# ClassDesign.net
KiCad netlist of a schematic drawn in Altium Designer
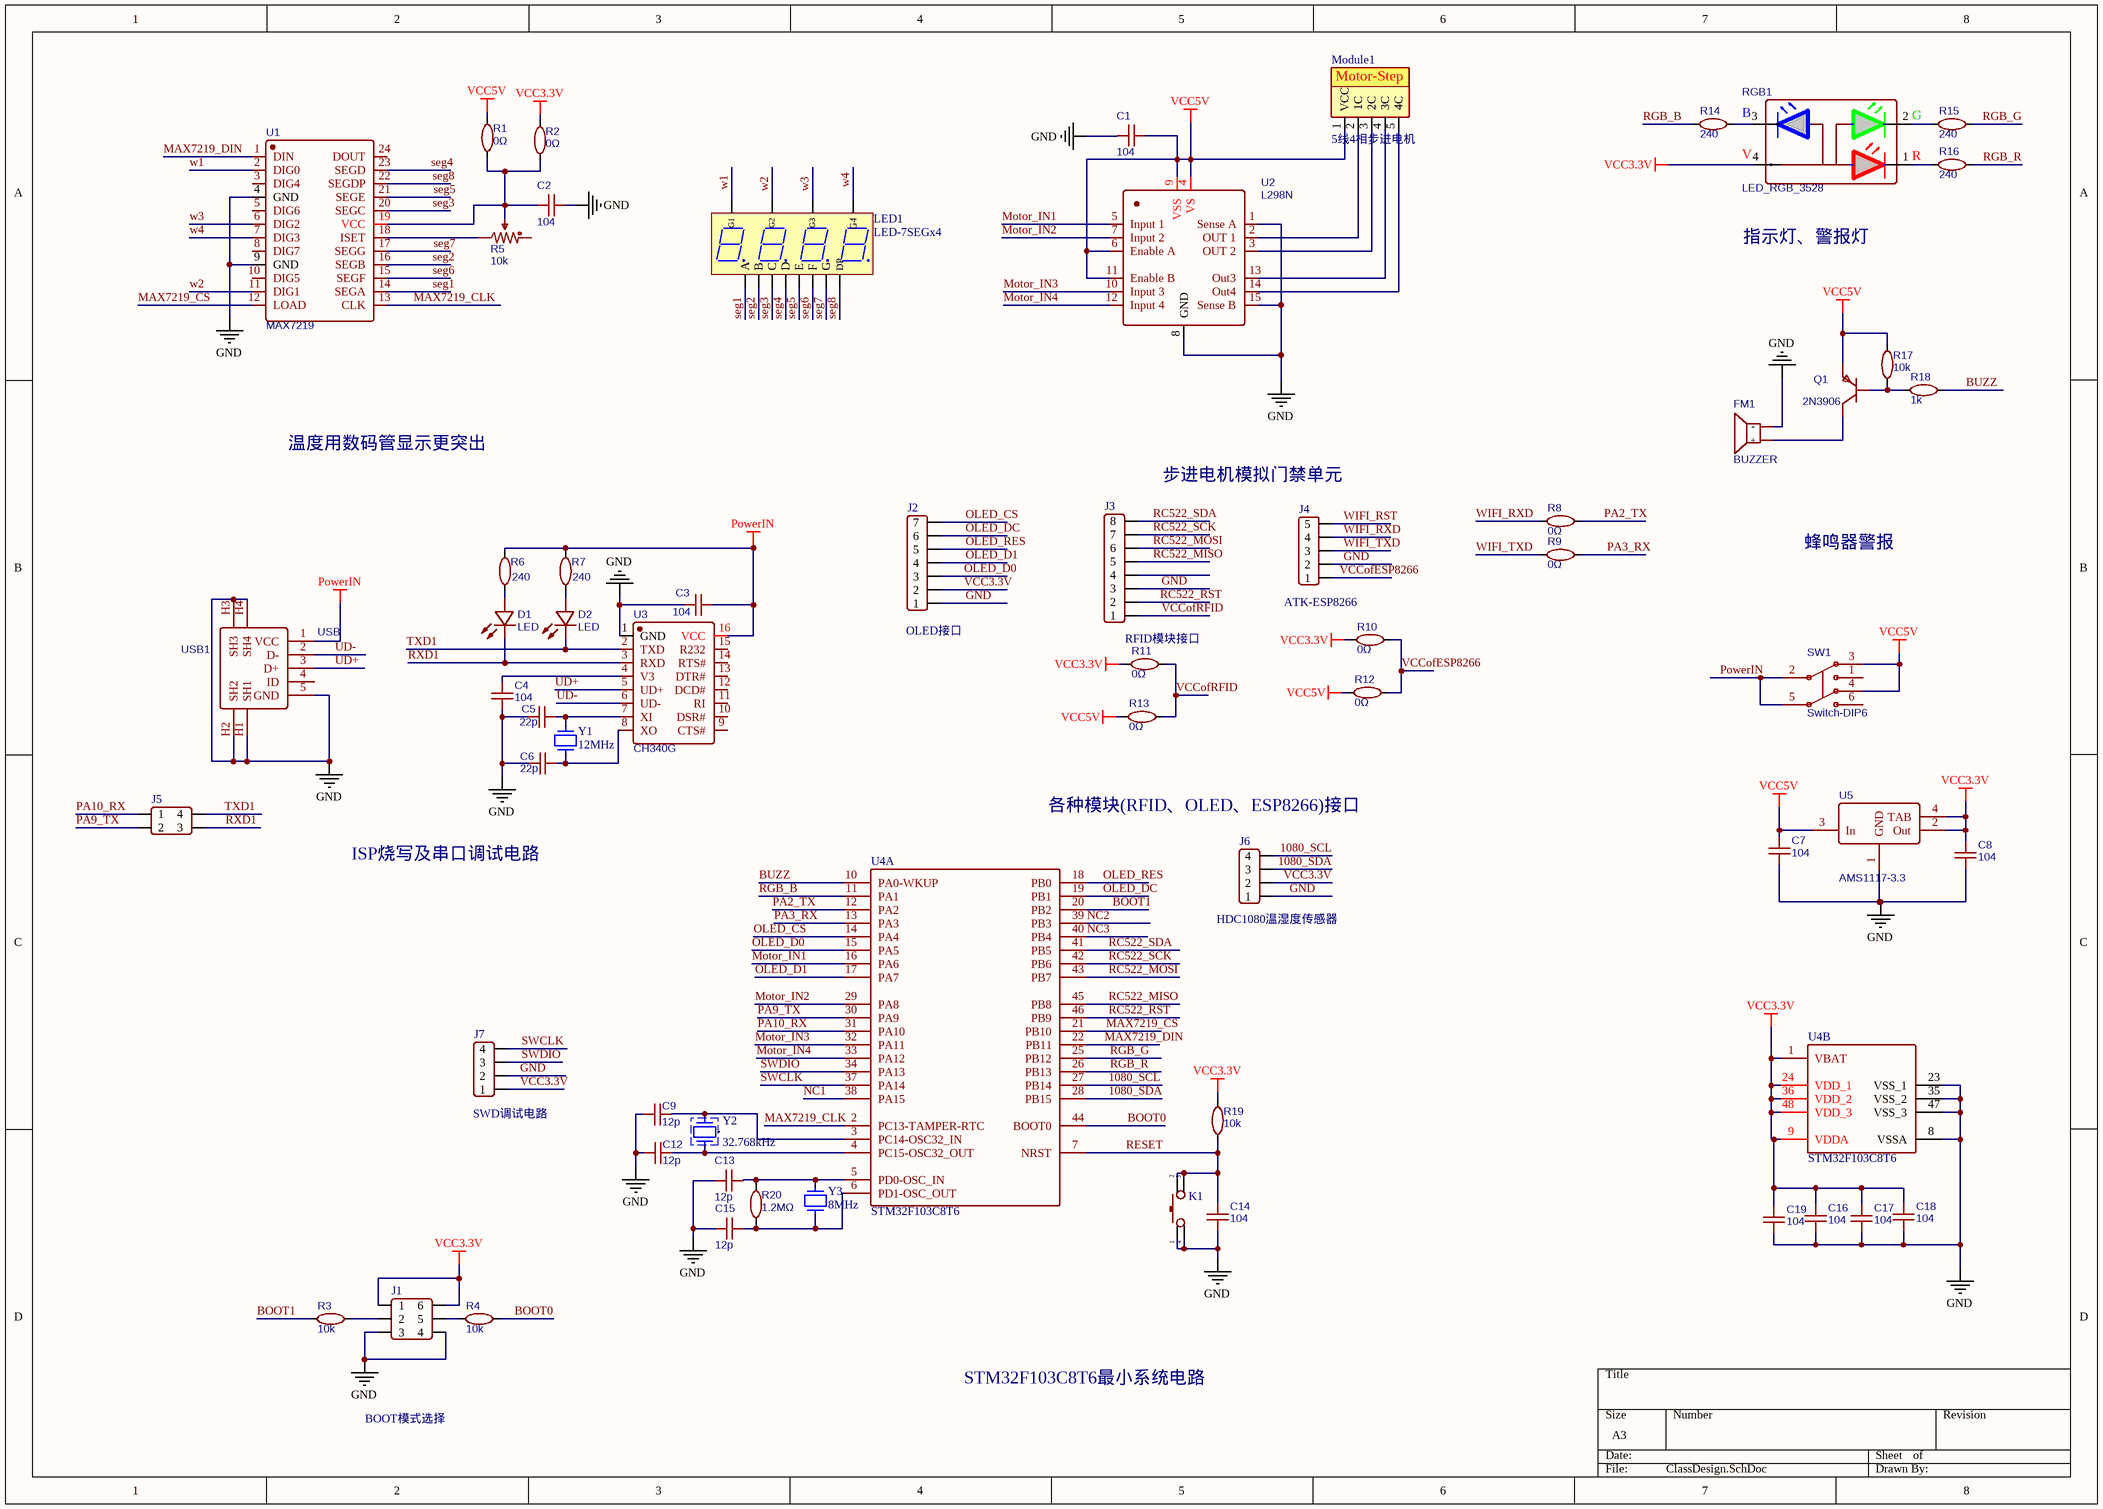
[diagram p0: ClassDesign.SchDoc]

(export (version "E")
  (design (tool "Eeschema 10.0.6"))
  (components
    (comp (ref "C1")
      (value "104")
      (footprint "CAP_0805")
      (fields
        (field (name "BOM_SUPPLIER PART") "C307348")
        (field (name "BOM_MANUFACTURER PART") "CL10B104KB8WPNC")
        (field (name "CONTRIBUTOR") "LCSC")
      )
      (libsource (lib "LTC_Library1") (part "CAP_0805"))
    )
    (comp (ref "C2")
      (value "104")
      (footprint "CAP_0805")
      (fields
        (field (name "BOM_SUPPLIER PART") "C307348")
        (field (name "BOM_MANUFACTURER PART") "CL10B104KB8WPNC")
        (field (name "CONTRIBUTOR") "LCSC")
      )
      (libsource (lib "LTC_Library1") (part "CAP_0805"))
    )
    (comp (ref "C3")
      (value "104")
      (footprint "CAP_0805")
      (fields
        (field (name "BOM_SUPPLIER PART") "C307348")
        (field (name "BOM_MANUFACTURER PART") "CL10B104KB8WPNC")
        (field (name "CONTRIBUTOR") "LCSC")
      )
      (libsource (lib "LTC_Library1") (part "CAP_0805"))
    )
    (comp (ref "C4")
      (value "104")
      (footprint "CAP_0805")
      (fields
        (field (name "BOM_SUPPLIER PART") "C307348")
        (field (name "BOM_MANUFACTURER PART") "CL10B104KB8WPNC")
        (field (name "CONTRIBUTOR") "LCSC")
      )
      (libsource (lib "LTC_Library1") (part "CAP_0805"))
    )
    (comp (ref "C5")
      (value "22p")
      (footprint "CAP_0805")
      (fields
        (field (name "BOM_SUPPLIER PART") "C307348")
        (field (name "BOM_MANUFACTURER PART") "CL10B104KB8WPNC")
        (field (name "CONTRIBUTOR") "LCSC")
      )
      (libsource (lib "LTC_Library1") (part "CAP_0805"))
    )
    (comp (ref "C6")
      (value "22p")
      (footprint "CAP_0805")
      (fields
        (field (name "BOM_SUPPLIER PART") "C307348")
        (field (name "BOM_MANUFACTURER PART") "CL10B104KB8WPNC")
        (field (name "CONTRIBUTOR") "LCSC")
      )
      (libsource (lib "LTC_Library1") (part "CAP_0805"))
    )
    (comp (ref "C7")
      (value "104")
      (footprint "CAP_0805")
      (fields
        (field (name "BOM_SUPPLIER PART") "C307348")
        (field (name "BOM_MANUFACTURER PART") "CL10B104KB8WPNC")
        (field (name "CONTRIBUTOR") "LCSC")
      )
      (libsource (lib "LTC_Library1") (part "CAP_0805"))
    )
    (comp (ref "C8")
      (value "104")
      (footprint "CAP_0805")
      (fields
        (field (name "BOM_SUPPLIER PART") "C307348")
        (field (name "BOM_MANUFACTURER PART") "CL10B104KB8WPNC")
        (field (name "CONTRIBUTOR") "LCSC")
      )
      (libsource (lib "LTC_Library1") (part "CAP_0805"))
    )
    (comp (ref "C9")
      (value "12p")
      (footprint "CAP_0805")
      (fields
        (field (name "BOM_SUPPLIER PART") "C307348")
        (field (name "BOM_MANUFACTURER PART") "CL10B104KB8WPNC")
        (field (name "CONTRIBUTOR") "LCSC")
      )
      (libsource (lib "LTC_Library1") (part "CAP_0805"))
    )
    (comp (ref "C12")
      (value "12p")
      (footprint "CAP_0805")
      (fields
        (field (name "BOM_SUPPLIER PART") "C307348")
        (field (name "BOM_MANUFACTURER PART") "CL10B104KB8WPNC")
        (field (name "CONTRIBUTOR") "LCSC")
      )
      (libsource (lib "LTC_Library1") (part "CAP_0805"))
    )
    (comp (ref "C13")
      (value "12p")
      (footprint "CAP_0805")
      (fields
        (field (name "BOM_SUPPLIER PART") "C307348")
        (field (name "BOM_MANUFACTURER PART") "CL10B104KB8WPNC")
        (field (name "CONTRIBUTOR") "LCSC")
      )
      (libsource (lib "LTC_Library1") (part "CAP_0805"))
    )
    (comp (ref "C14")
      (value "104")
      (footprint "CAP_0805")
      (fields
        (field (name "BOM_SUPPLIER PART") "C307348")
        (field (name "BOM_MANUFACTURER PART") "CL10B104KB8WPNC")
        (field (name "CONTRIBUTOR") "LCSC")
      )
      (libsource (lib "LTC_Library1") (part "CAP_0805"))
    )
    (comp (ref "C15")
      (value "12p")
      (footprint "CAP_0805")
      (fields
        (field (name "BOM_SUPPLIER PART") "C307348")
        (field (name "BOM_MANUFACTURER PART") "CL10B104KB8WPNC")
        (field (name "CONTRIBUTOR") "LCSC")
      )
      (libsource (lib "LTC_Library1") (part "CAP_0805"))
    )
    (comp (ref "C16")
      (value "104")
      (footprint "CAP_0805")
      (fields
        (field (name "BOM_SUPPLIER PART") "C307348")
        (field (name "BOM_MANUFACTURER PART") "CL10B104KB8WPNC")
        (field (name "CONTRIBUTOR") "LCSC")
      )
      (libsource (lib "LTC_Library1") (part "CAP_0805"))
    )
    (comp (ref "C17")
      (value "104")
      (footprint "CAP_0805")
      (fields
        (field (name "BOM_SUPPLIER PART") "C307348")
        (field (name "BOM_MANUFACTURER PART") "CL10B104KB8WPNC")
        (field (name "CONTRIBUTOR") "LCSC")
      )
      (libsource (lib "LTC_Library1") (part "CAP_0805"))
    )
    (comp (ref "C18")
      (value "104")
      (footprint "CAP_0805")
      (fields
        (field (name "BOM_SUPPLIER PART") "C307348")
        (field (name "BOM_MANUFACTURER PART") "CL10B104KB8WPNC")
        (field (name "CONTRIBUTOR") "LCSC")
      )
      (libsource (lib "LTC_Library1") (part "CAP_0805"))
    )
    (comp (ref "C19")
      (value "104")
      (footprint "CAP_0805")
      (fields
        (field (name "BOM_SUPPLIER PART") "C307348")
        (field (name "BOM_MANUFACTURER PART") "CL10B104KB8WPNC")
        (field (name "CONTRIBUTOR") "LCSC")
      )
      (libsource (lib "LTC_Library1") (part "CAP_0805"))
    )
    (comp (ref "D1")
      (value "LED")
      (footprint "LED_0805_R")
      (description "发光LED")
      (fields
        (field (name "BOM_MANUFACTURER PART") "D-G080508G1")
        (field (name "BOM_SUPPLIER PART") "C107402")
        (field (name "CONTRIBUTOR") "LCSC")
      )
      (libsource (lib "LTC_Library1") (part "LED_0805"))
    )
    (comp (ref "D2")
      (value "LED")
      (footprint "LED_0805_R")
      (description "发光LED")
      (fields
        (field (name "BOM_MANUFACTURER PART") "D-G080508G1")
        (field (name "BOM_SUPPLIER PART") "C107402")
        (field (name "CONTRIBUTOR") "LCSC")
      )
      (libsource (lib "LTC_Library1") (part "LED_0805"))
    )
    (comp (ref "FM1")
      (value "BUZZER")
      (footprint "BUZZ-12*7.5")
      (description "蜂鸣器")
      (fields (field (name "BOM_MANUFACTURER PART") "TMB12A12") (field (name "BOM_SUPPLIER PART") "C96079"))
      (libsource (lib "LTC_Library1") (part "BUZZER"))
    )
    (comp (ref "J1")
      (value "BOOT模式选择")
      (footprint "Header 2.54_2X3")
      (libsource (lib "LTC_Library1") (part "Header 2.54_2X3"))
    )
    (comp (ref "J2")
      (value "OLED接口")
      (footprint "Header 2.54X7")
      (libsource (lib "LTC_Library1") (part "Header 2.54_7"))
    )
    (comp (ref "J3")
      (value "RFID模块接口")
      (footprint "Header 2.54X8")
      (libsource (lib "Headers") (part "Header 2.54_8"))
    )
    (comp (ref "J4")
      (value "ATK-ESP8266")
      (footprint "Header 2.54X5")
      (libsource (lib "Headers") (part "Header 2.54_5"))
    )
    (comp (ref "J5")
      (value "Header 2.54_2X2")
      (footprint "Header 2.54_2x2")
      (libsource (lib "LTC_Library1") (part "Header 2.54_2X2"))
    )
    (comp (ref "J6")
      (value "HDC1080温湿度传感器")
      (footprint "Header 2.54X4")
      (libsource (lib "LTC_Library1") (part "Header 2.54_4"))
    )
    (comp (ref "J7")
      (value "SWD调试电路")
      (footprint "Header 2.54X4")
      (libsource (lib "LTC_Library1") (part "Header 2.54_4"))
    )
    (comp (ref "K1")
      (value "DIP-Button_4P")
      (footprint "TSW DIP-6*6*6")
      (description "按键，直插，6*6*6")
      (libsource (lib "LTC_Library1") (part "DIP-Button_4P"))
    )
    (comp (ref "LED1")
      (value "LED-7SEGx4")
      (footprint "DISP_0.56_4")
      (libsource (lib "LTC_Library1") (part "LED-7SEGx4"))
    )
    (comp (ref "Module1")
      (value "5线4相步进电机")
      (footprint "XH_2.54_5P")
      (libsource (lib "Module") (part "5线4相步进电机"))
    )
    (comp (ref "Q1")
      (value "2N3906")
      (footprint "TO_92A")
      (description "三极管PNP")
      (fields (field (name "BOM_SUPPLIER PART") "C305396") (field (name "CONTRIBUTOR") "LCSC"))
      (libsource (lib "LTC_Library1") (part "2N3906"))
    )
    (comp (ref "R1")
      (value "0Ω")
      (footprint "RES_0805")
      (fields
        (field (name "BOM_MANUFACTURER PART") "RC0402JR-07100KL")
        (field (name "BOM_SUPPLIER PART") "C106234")
      )
      (libsource (lib "LTC_Library1") (part "RES_0805"))
    )
    (comp (ref "R2")
      (value "0Ω")
      (footprint "RES_0805")
      (fields
        (field (name "BOM_MANUFACTURER PART") "RC0402JR-07100KL")
        (field (name "BOM_SUPPLIER PART") "C106234")
      )
      (libsource (lib "LTC_Library1") (part "RES_0805"))
    )
    (comp (ref "R3")
      (value "10k")
      (footprint "RES_0805")
      (fields
        (field (name "BOM_MANUFACTURER PART") "RC0402JR-07100KL")
        (field (name "BOM_SUPPLIER PART") "C106234")
      )
      (libsource (lib "LTC_Library1") (part "RES_0805"))
    )
    (comp (ref "R4")
      (value "10k")
      (footprint "RES_0805")
      (fields
        (field (name "BOM_MANUFACTURER PART") "RC0402JR-07100KL")
        (field (name "BOM_SUPPLIER PART") "C106234")
      )
      (libsource (lib "LTC_Library1") (part "RES_0805"))
    )
    (comp (ref "R5")
      (value "10k")
      (footprint "RES_POT-3362P")
      (description "可调电阻3362P")
      (fields
        (field (name "BOM_SUPPLIER PART") "C118947")
        (field (name "BOM_MANUFACTURER PART") "3362P-1-102")
        (field (name "CONTRIBUTOR") "LCSC")
      )
      (libsource (lib "LTC_Library1") (part "RES_POT-3362P"))
    )
    (comp (ref "R6")
      (value "240")
      (footprint "RES_0805")
      (fields
        (field (name "BOM_MANUFACTURER PART") "RC0402JR-07100KL")
        (field (name "BOM_SUPPLIER PART") "C106234")
      )
      (libsource (lib "LTC_Library1") (part "RES_0805"))
    )
    (comp (ref "R7")
      (value "240")
      (footprint "RES_0805")
      (fields
        (field (name "BOM_MANUFACTURER PART") "RC0402JR-07100KL")
        (field (name "BOM_SUPPLIER PART") "C106234")
      )
      (libsource (lib "LTC_Library1") (part "RES_0805"))
    )
    (comp (ref "R8")
      (value "0Ω")
      (footprint "RES_0805")
      (fields
        (field (name "BOM_MANUFACTURER PART") "RC0402JR-07100KL")
        (field (name "BOM_SUPPLIER PART") "C106234")
      )
      (libsource (lib "LTC_Library1") (part "RES_0805"))
    )
    (comp (ref "R9")
      (value "0Ω")
      (footprint "RES_0805")
      (fields
        (field (name "BOM_MANUFACTURER PART") "RC0402JR-07100KL")
        (field (name "BOM_SUPPLIER PART") "C106234")
      )
      (libsource (lib "LTC_Library1") (part "RES_0805"))
    )
    (comp (ref "R10")
      (value "0Ω")
      (footprint "RES_0805")
      (fields
        (field (name "BOM_MANUFACTURER PART") "RC0402JR-07100KL")
        (field (name "BOM_SUPPLIER PART") "C106234")
      )
      (libsource (lib "LTC_Library1") (part "RES_0805"))
    )
    (comp (ref "R11")
      (value "0Ω")
      (footprint "RES_0805")
      (fields
        (field (name "BOM_MANUFACTURER PART") "RC0402JR-07100KL")
        (field (name "BOM_SUPPLIER PART") "C106234")
      )
      (libsource (lib "LTC_Library1") (part "RES_0805"))
    )
    (comp (ref "R12")
      (value "0Ω")
      (footprint "RES_0805")
      (fields
        (field (name "BOM_MANUFACTURER PART") "RC0402JR-07100KL")
        (field (name "BOM_SUPPLIER PART") "C106234")
      )
      (libsource (lib "LTC_Library1") (part "RES_0805"))
    )
    (comp (ref "R13")
      (value "0Ω")
      (footprint "RES_0805")
      (fields
        (field (name "BOM_MANUFACTURER PART") "RC0402JR-07100KL")
        (field (name "BOM_SUPPLIER PART") "C106234")
      )
      (libsource (lib "LTC_Library1") (part "RES_0805"))
    )
    (comp (ref "R14")
      (value "240")
      (footprint "RES_0805")
      (fields
        (field (name "BOM_MANUFACTURER PART") "RC0402JR-07100KL")
        (field (name "BOM_SUPPLIER PART") "C106234")
      )
      (libsource (lib "LTC_Library1") (part "RES_0805"))
    )
    (comp (ref "R15")
      (value "240")
      (footprint "RES_0805")
      (fields
        (field (name "BOM_MANUFACTURER PART") "RC0402JR-07100KL")
        (field (name "BOM_SUPPLIER PART") "C106234")
      )
      (libsource (lib "LTC_Library1") (part "RES_0805"))
    )
    (comp (ref "R16")
      (value "240")
      (footprint "RES_0805")
      (fields
        (field (name "BOM_MANUFACTURER PART") "RC0402JR-07100KL")
        (field (name "BOM_SUPPLIER PART") "C106234")
      )
      (libsource (lib "LTC_Library1") (part "RES_0805"))
    )
    (comp (ref "R17")
      (value "10k")
      (footprint "RES_0805")
      (fields
        (field (name "BOM_MANUFACTURER PART") "RC0402JR-07100KL")
        (field (name "BOM_SUPPLIER PART") "C106234")
      )
      (libsource (lib "LTC_Library1") (part "RES_0805"))
    )
    (comp (ref "R18")
      (value "1k")
      (footprint "RES_0805")
      (fields
        (field (name "BOM_MANUFACTURER PART") "RC0402JR-07100KL")
        (field (name "BOM_SUPPLIER PART") "C106234")
      )
      (libsource (lib "LTC_Library1") (part "RES_0805"))
    )
    (comp (ref "R19")
      (value "10k")
      (footprint "RES_0805")
      (fields
        (field (name "BOM_MANUFACTURER PART") "RC0402JR-07100KL")
        (field (name "BOM_SUPPLIER PART") "C106234")
      )
      (libsource (lib "LTC_Library1") (part "RES_0805"))
    )
    (comp (ref "R20")
      (value "1.2MΩ")
      (footprint "RES_0805")
      (fields
        (field (name "BOM_MANUFACTURER PART") "RC0402JR-07100KL")
        (field (name "BOM_SUPPLIER PART") "C106234")
      )
      (libsource (lib "LTC_Library1") (part "RES_0805"))
    )
    (comp (ref "RGB1")
      (value "LED_RGB_3528")
      (footprint "LED_3528_RGB")
      (fields
        (field (name "BOM_MANUFACTURER PART") "FM-3528RGBA-HF")
        (field (name "BOM_SUPPLIER PART") "C108539")
        (field (name "CONTRIBUTOR") "LCSC")
      )
      (libsource (lib "LTC_Library1") (part "LED_RGB_3528"))
    )
    (comp (ref "SW1")
      (value "Switch-DIP6")
      (footprint "Switch_6")
      (description "6脚自锁开关")
      (fields (field (name "BOM_MANUFACTURER PART") "ESB33535") (field (name "BOM_SUPPLIER PART") "C79134"))
      (libsource (lib "LTC_Library1") (part "Switch-DIP6"))
    )
    (comp (ref "U1")
      (value "MAX7219")
      (footprint "SOIC_24W")
      (fields (field (name "BOM_MANUFACTURER PART") "max7219cng") (field (name "BOM_SUPPLIER PART") "C29160"))
      (libsource (lib "LTC_Library1") (part "MAX7219"))
    )
    (comp (ref "U2")
      (value "L298N")
      (footprint "Multiwatt_15")
      (fields (field (name "BOM_SUPPLIER PART") "C434589") (field (name "CONTRIBUTOR") "LCSC"))
      (libsource (lib "Driver IC") (part "L298N"))
    )
    (comp (ref "U3")
      (value "CH340G")
      (footprint "SOP-16")
      (fields (field (name "BOM_SUPPLIER PART") "C14267"))
      (libsource (lib "LTC_Library1") (part "CH340G"))
    )
    (comp (ref "U4")
      (value "STM32F103C8T6")
      (footprint "LQFP_48_7X7")
      (libsource (lib "MCU") (part "STM32F103C8T6"))
    )
    (comp (ref "U5")
      (value "AMS1117-3.3")
      (footprint "SOT-223_3")
      (fields (field (name "BOM_SUPPLIER PART") "C165482") (field (name "CONTRIBUTOR") "LCSC"))
      (libsource (lib "LTC_Library1") (part "AMS1117-3.3"))
    )
    (comp (ref "USB1")
      (value "USB")
      (footprint "USB_Micro_DIP41")
      (fields
        (field (name "BOM_SUPPLIER PART") "C404969")
        (field (name "BOM_MANUFACTURER PART") "MicroXNJ")
        (field (name "CONTRIBUTOR") "LCSC")
      )
      (libsource (lib "LTC_Library1") (part "MicroUSB"))
    )
    (comp (ref "Y1")
      (value "12MHz")
      (footprint "XTAL1")
      (description "晶振")
      (libsource (lib "LTC_Library1") (part "XTAL-2"))
    )
    (comp (ref "Y2")
      (value "32.768kHz")
      (footprint "XTAL-D2X6")
      (description "晶振3脚")
      (libsource (lib "LTC_Library1") (part "XTAL-3"))
    )
    (comp (ref "Y3")
      (value "8MHz")
      (footprint "XTAL1")
      (description "晶振")
      (libsource (lib "LTC_Library1") (part "XTAL-2"))
    )
  )
  (nets
    (net (code "1") (name "/1080_SCL") (class "Default")
      (node (ref "J6") (pin "4") (pinfunction "4_4") (pintype "passive"))
      (node (ref "U4") (pin "27") (pinfunction "PB14_27") (pintype "passive"))
    )
    (net (code "2") (name "/1080_SDA") (class "Default")
      (node (ref "J6") (pin "3") (pinfunction "3_3") (pintype "passive"))
      (node (ref "U4") (pin "28") (pinfunction "PB15_28") (pintype "passive"))
    )
    (net (code "3") (name "/BOOT0") (class "Default")
      (node (ref "R4") (pin "2") (pinfunction "2_2") (pintype "passive"))
      (node (ref "U4") (pin "44") (pinfunction "BOOT0_44") (pintype "passive"))
    )
    (net (code "4") (name "/BOOT1") (class "Default")
      (node (ref "R3") (pin "1") (pinfunction "1_1") (pintype "passive"))
      (node (ref "U4") (pin "20") (pinfunction "PB2_20") (pintype "passive"))
    )
    (net (code "5") (name "/BUZZ") (class "Default")
      (node (ref "R18") (pin "2") (pinfunction "2_2") (pintype "passive"))
      (node (ref "U4") (pin "10") (pinfunction "PA0-WKUP_10") (pintype "passive"))
    )
    (net (code "6") (name "/MAX7219_CLK") (class "Default")
      (node (ref "U1") (pin "13") (pinfunction "CLK_13") (pintype "passive"))
      (node (ref "U4") (pin "2") (pinfunction "PC13-TAMPER-RTC_2") (pintype "passive"))
    )
    (net (code "7") (name "/MAX7219_CS") (class "Default")
      (node (ref "U1") (pin "12") (pinfunction "LOAD_12") (pintype "passive"))
      (node (ref "U4") (pin "21") (pinfunction "PB10_21") (pintype "passive"))
    )
    (net (code "8") (name "/MAX7219_DIN") (class "Default")
      (node (ref "U1") (pin "1") (pinfunction "DIN_1") (pintype "passive"))
      (node (ref "U4") (pin "22") (pinfunction "PB11_22") (pintype "passive"))
    )
    (net (code "9") (name "/Motor_IN1") (class "Default")
      (node (ref "U2") (pin "5") (pinfunction "Input_1_5") (pintype "passive"))
      (node (ref "U4") (pin "16") (pinfunction "PA6_16") (pintype "passive"))
    )
    (net (code "10") (name "/Motor_IN2") (class "Default")
      (node (ref "U2") (pin "7") (pinfunction "Input_2_7") (pintype "passive"))
      (node (ref "U4") (pin "29") (pinfunction "PA8_29") (pintype "passive"))
    )
    (net (code "11") (name "/Motor_IN3") (class "Default")
      (node (ref "U2") (pin "10") (pinfunction "Input_3_10") (pintype "passive"))
      (node (ref "U4") (pin "32") (pinfunction "PA11_32") (pintype "passive"))
    )
    (net (code "12") (name "/Motor_IN4") (class "Default")
      (node (ref "U2") (pin "12") (pinfunction "Input_4_12") (pintype "passive"))
      (node (ref "U4") (pin "33") (pinfunction "PA12_33") (pintype "passive"))
    )
    (net (code "13") (name "/NC1") (class "Default")
      (node (ref "U4") (pin "38") (pinfunction "PA15_38") (pintype "passive"))
    )
    (net (code "14") (name "/NC2") (class "Default")
      (node (ref "U4") (pin "39") (pinfunction "PB3_39") (pintype "passive"))
    )
    (net (code "15") (name "/NC3") (class "Default")
      (node (ref "U4") (pin "40") (pinfunction "PB4_40") (pintype "passive"))
    )
    (net (code "16") (name "/OLED_CS") (class "Default")
      (node (ref "J2") (pin "7") (pinfunction "7_7") (pintype "passive"))
      (node (ref "U4") (pin "14") (pinfunction "PA4_14") (pintype "passive"))
    )
    (net (code "17") (name "/OLED_D0") (class "Default")
      (node (ref "J2") (pin "3") (pinfunction "3_3") (pintype "passive"))
      (node (ref "U4") (pin "15") (pinfunction "PA5_15") (pintype "passive"))
    )
    (net (code "18") (name "/OLED_D1") (class "Default")
      (node (ref "J2") (pin "4") (pinfunction "4_4") (pintype "passive"))
      (node (ref "U4") (pin "17") (pinfunction "PA7_17") (pintype "passive"))
    )
    (net (code "19") (name "/OLED_DC") (class "Default")
      (node (ref "J2") (pin "6") (pinfunction "6_6") (pintype "passive"))
      (node (ref "U4") (pin "19") (pinfunction "PB1_19") (pintype "passive"))
    )
    (net (code "20") (name "/OLED_RES") (class "Default")
      (node (ref "J2") (pin "5") (pinfunction "5_5") (pintype "passive"))
      (node (ref "U4") (pin "18") (pinfunction "PB0_18") (pintype "passive"))
    )
    (net (code "21") (name "/PA2_TX") (class "Default")
      (node (ref "R8") (pin "2") (pinfunction "2_2") (pintype "passive"))
      (node (ref "U4") (pin "12") (pinfunction "PA2_12") (pintype "passive"))
    )
    (net (code "22") (name "/PA3_RX") (class "Default")
      (node (ref "R9") (pin "2") (pinfunction "2_2") (pintype "passive"))
      (node (ref "U4") (pin "13") (pinfunction "PA3_13") (pintype "passive"))
    )
    (net (code "23") (name "/PA9_TX") (class "Default")
      (node (ref "J5") (pin "2") (pinfunction "2_2") (pintype "passive"))
      (node (ref "U4") (pin "30") (pinfunction "PA9_30") (pintype "passive"))
    )
    (net (code "24") (name "/PA10_RX") (class "Default")
      (node (ref "J5") (pin "1") (pinfunction "1_1") (pintype "passive"))
      (node (ref "U4") (pin "31") (pinfunction "PA10_31") (pintype "passive"))
    )
    (net (code "25") (name "/RC522_MISO") (class "Default")
      (node (ref "J3") (pin "5") (pinfunction "5_5") (pintype "passive"))
      (node (ref "U4") (pin "45") (pinfunction "PB8_45") (pintype "passive"))
    )
    (net (code "26") (name "/RC522_MOSI") (class "Default")
      (node (ref "J3") (pin "6") (pinfunction "6_6") (pintype "passive"))
      (node (ref "U4") (pin "43") (pinfunction "PB7_43") (pintype "passive"))
    )
    (net (code "27") (name "/RC522_RST") (class "Default")
      (node (ref "J3") (pin "2") (pinfunction "2_2") (pintype "passive"))
      (node (ref "U4") (pin "46") (pinfunction "PB9_46") (pintype "passive"))
    )
    (net (code "28") (name "/RC522_SCK") (class "Default")
      (node (ref "J3") (pin "7") (pinfunction "7_7") (pintype "passive"))
      (node (ref "U4") (pin "42") (pinfunction "PB6_42") (pintype "passive"))
    )
    (net (code "29") (name "/RC522_SDA") (class "Default")
      (node (ref "J3") (pin "8") (pinfunction "8_8") (pintype "passive"))
      (node (ref "U4") (pin "41") (pinfunction "PB5_41") (pintype "passive"))
    )
    (net (code "30") (name "/RESET") (class "Default")
      (node (ref "C14") (pin "1") (pinfunction "1_1") (pintype "passive"))
      (node (ref "K1") (pin "2") (pintype "passive"))
      (node (ref "K1") (pin "3") (pintype "passive"))
      (node (ref "R19") (pin "1") (pinfunction "1_1") (pintype "passive"))
      (node (ref "U4") (pin "7") (pinfunction "NRST_7") (pintype "passive"))
    )
    (net (code "31") (name "/RGB_B") (class "Default")
      (node (ref "R14") (pin "2") (pinfunction "2_2") (pintype "passive"))
      (node (ref "U4") (pin "11") (pinfunction "PA1_11") (pintype "passive"))
    )
    (net (code "32") (name "/RGB_G") (class "Default")
      (node (ref "R15") (pin "2") (pinfunction "2_2") (pintype "passive"))
      (node (ref "U4") (pin "25") (pinfunction "PB12_25") (pintype "passive"))
    )
    (net (code "33") (name "/RGB_R") (class "Default")
      (node (ref "R16") (pin "2") (pinfunction "2_2") (pintype "passive"))
      (node (ref "U4") (pin "26") (pinfunction "PB13_26") (pintype "passive"))
    )
    (net (code "34") (name "/RXD1") (class "Default")
      (node (ref "D1") (pin "C") (pinfunction "C_C") (pintype "passive"))
      (node (ref "J5") (pin "3") (pinfunction "3_3") (pintype "passive"))
      (node (ref "U3") (pin "3") (pinfunction "RXD_3") (pintype "passive"))
    )
    (net (code "35") (name "/SWCLK") (class "Default")
      (node (ref "J7") (pin "4") (pinfunction "4_4") (pintype "passive"))
      (node (ref "U4") (pin "37") (pinfunction "PA14_37") (pintype "passive"))
    )
    (net (code "36") (name "/SWDIO") (class "Default")
      (node (ref "J7") (pin "3") (pinfunction "3_3") (pintype "passive"))
      (node (ref "U4") (pin "34") (pinfunction "PA13_34") (pintype "passive"))
    )
    (net (code "37") (name "/TXD1") (class "Default")
      (node (ref "D2") (pin "C") (pinfunction "C_C") (pintype "passive"))
      (node (ref "J5") (pin "4") (pinfunction "4_4") (pintype "passive"))
      (node (ref "U3") (pin "2") (pinfunction "TXD_2") (pintype "passive"))
    )
    (net (code "38") (name "/UD+") (class "Default")
      (node (ref "U3") (pin "5") (pinfunction "UD+_5") (pintype "passive"))
      (node (ref "USB1") (pin "3") (pinfunction "D+_3") (pintype "passive"))
    )
    (net (code "39") (name "/UD-") (class "Default")
      (node (ref "U3") (pin "6") (pinfunction "UD-_6") (pintype "passive"))
      (node (ref "USB1") (pin "2") (pinfunction "D-_2") (pintype "passive"))
    )
    (net (code "40") (name "/VCCofESP8266") (class "Default")
      (node (ref "J4") (pin "1") (pinfunction "1_1") (pintype "passive"))
      (node (ref "R10") (pin "1") (pinfunction "1_1") (pintype "passive"))
      (node (ref "R12") (pin "1") (pinfunction "1_1") (pintype "passive"))
    )
    (net (code "41") (name "/VCCofRFID") (class "Default")
      (node (ref "J3") (pin "1") (pinfunction "1_1") (pintype "passive"))
      (node (ref "R11") (pin "1") (pinfunction "1_1") (pintype "passive"))
      (node (ref "R13") (pin "1") (pinfunction "1_1") (pintype "passive"))
    )
    (net (code "42") (name "/WIFI_RST") (class "Default")
      (node (ref "J4") (pin "5") (pinfunction "5_5") (pintype "passive"))
    )
    (net (code "43") (name "/WIFI_RXD") (class "Default")
      (node (ref "J4") (pin "4") (pinfunction "4_4") (pintype "passive"))
      (node (ref "R8") (pin "1") (pinfunction "1_1") (pintype "passive"))
    )
    (net (code "44") (name "/WIFI_TXD") (class "Default")
      (node (ref "J4") (pin "3") (pinfunction "3_3") (pintype "passive"))
      (node (ref "R9") (pin "1") (pinfunction "1_1") (pintype "passive"))
    )
    (net (code "45") (name "/seg1") (class "Default")
      (node (ref "LED1") (pin "11") (pinfunction "A_11") (pintype "passive"))
      (node (ref "U1") (pin "14") (pinfunction "SEGA_14") (pintype "passive"))
    )
    (net (code "46") (name "/seg2") (class "Default")
      (node (ref "LED1") (pin "7") (pinfunction "B_7") (pintype "passive"))
      (node (ref "U1") (pin "16") (pinfunction "SEGB_16") (pintype "passive"))
    )
    (net (code "47") (name "/seg3") (class "Default")
      (node (ref "LED1") (pin "4") (pinfunction "C_4") (pintype "passive"))
      (node (ref "U1") (pin "20") (pinfunction "SEGC_20") (pintype "passive"))
    )
    (net (code "48") (name "/seg4") (class "Default")
      (node (ref "LED1") (pin "2") (pinfunction "D_2") (pintype "passive"))
      (node (ref "U1") (pin "23") (pinfunction "SEGD_23") (pintype "passive"))
    )
    (net (code "49") (name "/seg5") (class "Default")
      (node (ref "LED1") (pin "1") (pinfunction "E_1") (pintype "passive"))
      (node (ref "U1") (pin "21") (pinfunction "SEGE_21") (pintype "passive"))
    )
    (net (code "50") (name "/seg6") (class "Default")
      (node (ref "LED1") (pin "10") (pinfunction "F_10") (pintype "passive"))
      (node (ref "U1") (pin "15") (pinfunction "SEGF_15") (pintype "passive"))
    )
    (net (code "51") (name "/seg7") (class "Default")
      (node (ref "LED1") (pin "5") (pinfunction "G_5") (pintype "passive"))
      (node (ref "U1") (pin "17") (pinfunction "SEGG_17") (pintype "passive"))
    )
    (net (code "52") (name "/seg8") (class "Default")
      (node (ref "LED1") (pin "3") (pinfunction "DP_3") (pintype "passive"))
      (node (ref "U1") (pin "22") (pinfunction "SEGDP_22") (pintype "passive"))
    )
    (net (code "53") (name "/w1") (class "Default")
      (node (ref "LED1") (pin "12") (pinfunction "G1_12") (pintype "passive"))
      (node (ref "U1") (pin "2") (pinfunction "DIG0_2") (pintype "passive"))
    )
    (net (code "54") (name "/w2") (class "Default")
      (node (ref "LED1") (pin "9") (pinfunction "G2_9") (pintype "passive"))
      (node (ref "U1") (pin "11") (pinfunction "DIG1_11") (pintype "passive"))
    )
    (net (code "55") (name "/w3") (class "Default")
      (node (ref "LED1") (pin "8") (pinfunction "G3_8") (pintype "passive"))
      (node (ref "U1") (pin "6") (pinfunction "DIG2_6") (pintype "passive"))
    )
    (net (code "56") (name "/w4") (class "Default")
      (node (ref "LED1") (pin "6") (pinfunction "G4_6") (pintype "passive"))
      (node (ref "U1") (pin "7") (pinfunction "DIG3_7") (pintype "passive"))
    )
    (net (code "57") (name "GND") (class "Default")
      (node (ref "C1") (pin "1") (pinfunction "1_1") (pintype "passive"))
      (node (ref "C12") (pin "1") (pinfunction "1_1") (pintype "passive"))
      (node (ref "C13") (pin "2") (pinfunction "2_2") (pintype "passive"))
      (node (ref "C14") (pin "2") (pinfunction "2_2") (pintype "passive"))
      (node (ref "C15") (pin "2") (pinfunction "2_2") (pintype "passive"))
      (node (ref "C16") (pin "2") (pinfunction "2_2") (pintype "passive"))
      (node (ref "C17") (pin "2") (pinfunction "2_2") (pintype "passive"))
      (node (ref "C18") (pin "2") (pinfunction "2_2") (pintype "passive"))
      (node (ref "C19") (pin "2") (pinfunction "2_2") (pintype "passive"))
      (node (ref "C2") (pin "2") (pinfunction "2_2") (pintype "passive"))
      (node (ref "C3") (pin "2") (pinfunction "2_2") (pintype "passive"))
      (node (ref "C4") (pin "1") (pinfunction "1_1") (pintype "passive"))
      (node (ref "C5") (pin "1") (pinfunction "1_1") (pintype "passive"))
      (node (ref "C6") (pin "1") (pinfunction "1_1") (pintype "passive"))
      (node (ref "C7") (pin "2") (pinfunction "2_2") (pintype "passive"))
      (node (ref "C8") (pin "2") (pinfunction "2_2") (pintype "passive"))
      (node (ref "C9") (pin "1") (pinfunction "1_1") (pintype "passive"))
      (node (ref "FM1") (pin "2") (pinfunction "－_2") (pintype "passive"))
      (node (ref "J1") (pin "3") (pinfunction "3_3") (pintype "passive"))
      (node (ref "J1") (pin "4") (pinfunction "4_4") (pintype "passive"))
      (node (ref "J2") (pin "1") (pinfunction "1_1") (pintype "passive"))
      (node (ref "J3") (pin "3") (pinfunction "3_3") (pintype "passive"))
      (node (ref "J4") (pin "2") (pinfunction "2_2") (pintype "passive"))
      (node (ref "J6") (pin "1") (pinfunction "1_1") (pintype "passive"))
      (node (ref "J7") (pin "2") (pinfunction "2_2") (pintype "passive"))
      (node (ref "K1") (pin "1") (pintype "passive"))
      (node (ref "K1") (pin "4") (pintype "passive"))
      (node (ref "U1") (pin "4") (pinfunction "GND_4") (pintype "passive"))
      (node (ref "U1") (pin "9") (pinfunction "GND_9") (pintype "passive"))
      (node (ref "U2") (pin "1") (pinfunction "Sense_A_1") (pintype "passive"))
      (node (ref "U2") (pin "15") (pinfunction "Sense_B_15") (pintype "passive"))
      (node (ref "U2") (pin "8") (pinfunction "GND_8") (pintype "passive"))
      (node (ref "U3") (pin "1") (pinfunction "GND_1") (pintype "passive"))
      (node (ref "U4") (pin "23") (pinfunction "VSS_1_23") (pintype "passive"))
      (node (ref "U4") (pin "35") (pinfunction "VSS_2_35") (pintype "passive"))
      (node (ref "U4") (pin "47") (pinfunction "VSS_3_47") (pintype "passive"))
      (node (ref "U4") (pin "8") (pinfunction "VSSA_8") (pintype "passive"))
      (node (ref "U5") (pin "1") (pinfunction "GND_1") (pintype "passive"))
      (node (ref "USB1") (pin "5") (pinfunction "GND_5") (pintype "passive"))
      (node (ref "USB1") (pin "H1") (pinfunction "SH1_H1") (pintype "passive"))
      (node (ref "USB1") (pin "H2") (pinfunction "SH2_H2") (pintype "passive"))
      (node (ref "USB1") (pin "H3") (pinfunction "SH3_H3") (pintype "passive"))
      (node (ref "USB1") (pin "H4") (pinfunction "SH4_H4") (pintype "passive"))
    )
    (net (code "58") (name "Net-(D1-PadA)") (class "Default")
      (node (ref "D1") (pin "A") (pinfunction "A_A") (pintype "passive"))
      (node (ref "R6") (pin "1") (pinfunction "1_1") (pintype "passive"))
    )
    (net (code "59") (name "Net-(D2-PadA)") (class "Default")
      (node (ref "D2") (pin "A") (pinfunction "A_A") (pintype "passive"))
      (node (ref "R7") (pin "1") (pinfunction "1_1") (pintype "passive"))
    )
    (net (code "60") (name "Net-(FM1-+)") (class "Default")
      (node (ref "FM1") (pin "1") (pinfunction "+_1") (pintype "passive"))
      (node (ref "Q1") (pin "3") (pinfunction "C_3") (pintype "passive"))
    )
    (net (code "61") (name "Net-(J1-Pad2)") (class "Default")
      (node (ref "J1") (pin "2") (pinfunction "2_2") (pintype "passive"))
      (node (ref "R3") (pin "2") (pinfunction "2_2") (pintype "passive"))
    )
    (net (code "62") (name "Net-(J1-Pad5)") (class "Default")
      (node (ref "J1") (pin "5") (pinfunction "5_5") (pintype "passive"))
      (node (ref "R4") (pin "1") (pinfunction "1_1") (pintype "passive"))
    )
    (net (code "63") (name "Net-(Module1-1C)") (class "Default")
      (node (ref "Module1") (pin "2") (pinfunction "1C_2") (pintype "passive"))
      (node (ref "U2") (pin "2") (pinfunction "OUT_1_2") (pintype "passive"))
    )
    (net (code "64") (name "Net-(Module1-2C)") (class "Default")
      (node (ref "Module1") (pin "3") (pinfunction "2C_3") (pintype "passive"))
      (node (ref "U2") (pin "3") (pinfunction "OUT_2_3") (pintype "passive"))
    )
    (net (code "65") (name "Net-(Module1-3C)") (class "Default")
      (node (ref "Module1") (pin "4") (pinfunction "3C_4") (pintype "passive"))
      (node (ref "U2") (pin "13") (pinfunction "Out3_13") (pintype "passive"))
    )
    (net (code "66") (name "Net-(Module1-4C)") (class "Default")
      (node (ref "Module1") (pin "5") (pinfunction "4C_5") (pintype "passive"))
      (node (ref "U2") (pin "14") (pinfunction "Out4_14") (pintype "passive"))
    )
    (net (code "67") (name "Net-(Q1-B)") (class "Default")
      (node (ref "Q1") (pin "2") (pinfunction "B_2") (pintype "passive"))
      (node (ref "R17") (pin "1") (pinfunction "1_1") (pintype "passive"))
      (node (ref "R18") (pin "1") (pinfunction "1_1") (pintype "passive"))
    )
    (net (code "68") (name "Net-(R14-Pad1)") (class "Default")
      (node (ref "R14") (pin "1") (pinfunction "1_1") (pintype "passive"))
      (node (ref "RGB1") (pin "3") (pintype "passive"))
    )
    (net (code "69") (name "Net-(R15-Pad1)") (class "Default")
      (node (ref "R15") (pin "1") (pinfunction "1_1") (pintype "passive"))
      (node (ref "RGB1") (pin "2") (pintype "passive"))
    )
    (net (code "70") (name "Net-(R16-Pad1)") (class "Default")
      (node (ref "R16") (pin "1") (pinfunction "1_1") (pintype "passive"))
      (node (ref "RGB1") (pin "1") (pintype "passive"))
    )
    (net (code "71") (name "Net-(U1-ISET)") (class "Default")
      (node (ref "R5") (pin "1") (pinfunction "1_1") (pintype "passive"))
      (node (ref "U1") (pin "18") (pinfunction "ISET_18") (pintype "passive"))
    )
    (net (code "72") (name "Net-(U1-VCC)") (class "Default")
      (node (ref "C2") (pin "1") (pinfunction "1_1") (pintype "passive"))
      (node (ref "R1") (pin "1") (pinfunction "1_1") (pintype "passive"))
      (node (ref "R2") (pin "1") (pinfunction "1_1") (pintype "passive"))
      (node (ref "R5") (pin "2") (pinfunction "2_2") (pintype "passive"))
      (node (ref "U1") (pin "19") (pinfunction "VCC_19") (pintype "passive"))
    )
    (net (code "73") (name "Net-(U3-V3)") (class "Default")
      (node (ref "C4") (pin "2") (pinfunction "2_2") (pintype "passive"))
      (node (ref "U3") (pin "4") (pinfunction "V3_4") (pintype "passive"))
    )
    (net (code "74") (name "Net-(U3-XI)") (class "Default")
      (node (ref "C5") (pin "2") (pinfunction "2_2") (pintype "passive"))
      (node (ref "U3") (pin "7") (pinfunction "XI_7") (pintype "passive"))
      (node (ref "Y1") (pin "1") (pinfunction "1_1") (pintype "passive"))
    )
    (net (code "75") (name "Net-(U3-XO)") (class "Default")
      (node (ref "C6") (pin "2") (pinfunction "2_2") (pintype "passive"))
      (node (ref "U3") (pin "8") (pinfunction "XO_8") (pintype "passive"))
      (node (ref "Y1") (pin "2") (pinfunction "2_2") (pintype "passive"))
    )
    (net (code "76") (name "Net-(U4A-PC14-OSC32_IN)") (class "Default")
      (node (ref "C9") (pin "2") (pinfunction "2_2") (pintype "passive"))
      (node (ref "U4") (pin "3") (pinfunction "PC14-OSC32_IN_3") (pintype "passive"))
      (node (ref "Y2") (pin "2") (pinfunction "2_2") (pintype "passive"))
    )
    (net (code "77") (name "Net-(U4A-PC15-OSC32_OUT)") (class "Default")
      (node (ref "C12") (pin "2") (pinfunction "2_2") (pintype "passive"))
      (node (ref "U4") (pin "4") (pinfunction "PC15-OSC32_OUT_4") (pintype "passive"))
      (node (ref "Y2") (pin "1") (pinfunction "1_1") (pintype "passive"))
    )
    (net (code "78") (name "Net-(U4A-PD0-OSC_IN)") (class "Default")
      (node (ref "C13") (pin "1") (pinfunction "1_1") (pintype "passive"))
      (node (ref "R20") (pin "1") (pinfunction "1_1") (pintype "passive"))
      (node (ref "U4") (pin "5") (pinfunction "PD0-OSC_IN_5") (pintype "passive"))
      (node (ref "Y3") (pin "2") (pinfunction "2_2") (pintype "passive"))
    )
    (net (code "79") (name "Net-(U4A-PD1-OSC_OUT)") (class "Default")
      (node (ref "C15") (pin "1") (pinfunction "1_1") (pintype "passive"))
      (node (ref "R20") (pin "2") (pinfunction "2_2") (pintype "passive"))
      (node (ref "U4") (pin "6") (pinfunction "PD1-OSC_OUT_6") (pintype "passive"))
      (node (ref "Y3") (pin "1") (pinfunction "1_1") (pintype "passive"))
    )
    (net (code "80") (name "PowerIN") (class "Default")
      (node (ref "C3") (pin "1") (pinfunction "1_1") (pintype "passive"))
      (node (ref "R6") (pin "2") (pinfunction "2_2") (pintype "passive"))
      (node (ref "R7") (pin "2") (pinfunction "2_2") (pintype "passive"))
      (node (ref "SW1") (pin "2") (pinfunction "C_2") (pintype "passive"))
      (node (ref "SW1") (pin "5") (pinfunction "C_5") (pintype "passive"))
      (node (ref "U3") (pin "16") (pinfunction "VCC_16") (pintype "passive"))
      (node (ref "USB1") (pin "1") (pinfunction "VCC_1") (pintype "passive"))
    )
    (net (code "81") (name "VCC3.3V") (class "Default")
      (node (ref "C16") (pin "1") (pinfunction "1_1") (pintype "passive"))
      (node (ref "C17") (pin "1") (pinfunction "1_1") (pintype "passive"))
      (node (ref "C18") (pin "1") (pinfunction "1_1") (pintype "passive"))
      (node (ref "C19") (pin "1") (pinfunction "1_1") (pintype "passive"))
      (node (ref "C8") (pin "1") (pinfunction "1_1") (pintype "passive"))
      (node (ref "J1") (pin "1") (pinfunction "1_1") (pintype "passive"))
      (node (ref "J1") (pin "6") (pinfunction "6_6") (pintype "passive"))
      (node (ref "J2") (pin "2") (pinfunction "2_2") (pintype "passive"))
      (node (ref "J6") (pin "2") (pinfunction "2_2") (pintype "passive"))
      (node (ref "J7") (pin "1") (pinfunction "1_1") (pintype "passive"))
      (node (ref "R10") (pin "2") (pinfunction "2_2") (pintype "passive"))
      (node (ref "R11") (pin "2") (pinfunction "2_2") (pintype "passive"))
      (node (ref "R19") (pin "2") (pinfunction "2_2") (pintype "passive"))
      (node (ref "R2") (pin "2") (pinfunction "2_2") (pintype "passive"))
      (node (ref "RGB1") (pin "4") (pintype "passive"))
      (node (ref "U4") (pin "1") (pinfunction "VBAT_1") (pintype "passive"))
      (node (ref "U4") (pin "24") (pinfunction "VDD_1_24") (pintype "passive"))
      (node (ref "U4") (pin "36") (pinfunction "VDD_2_36") (pintype "passive"))
      (node (ref "U4") (pin "48") (pinfunction "VDD_3_48") (pintype "passive"))
      (node (ref "U4") (pin "9") (pinfunction "VDDA_9") (pintype "passive"))
      (node (ref "U5") (pin "2") (pinfunction "Out_2") (pintype "passive"))
      (node (ref "U5") (pin "4") (pinfunction "TAB_4") (pintype "passive"))
    )
    (net (code "82") (name "VCC5V") (class "Default")
      (node (ref "C1") (pin "2") (pinfunction "2_2") (pintype "passive"))
      (node (ref "C7") (pin "1") (pinfunction "1_1") (pintype "passive"))
      (node (ref "Module1") (pin "1") (pinfunction "VCC_1") (pintype "passive"))
      (node (ref "Q1") (pin "1") (pinfunction "E_1") (pintype "passive"))
      (node (ref "R1") (pin "2") (pinfunction "2_2") (pintype "passive"))
      (node (ref "R12") (pin "2") (pinfunction "2_2") (pintype "passive"))
      (node (ref "R13") (pin "2") (pinfunction "2_2") (pintype "passive"))
      (node (ref "R17") (pin "2") (pinfunction "2_2") (pintype "passive"))
      (node (ref "SW1") (pin "3") (pinfunction "NC_3") (pintype "passive"))
      (node (ref "SW1") (pin "4") (pinfunction "NC_4") (pintype "passive"))
      (node (ref "U2") (pin "11") (pinfunction "Enable_B_11") (pintype "passive"))
      (node (ref "U2") (pin "4") (pinfunction "VS_4") (pintype "passive"))
      (node (ref "U2") (pin "6") (pinfunction "Enable_A_6") (pintype "passive"))
      (node (ref "U2") (pin "9") (pinfunction "VSS_9") (pintype "passive"))
      (node (ref "U5") (pin "3") (pinfunction "In_3") (pintype "passive"))
    )
    (net (code "83") (name "unconnected-(J3-Pad4)") (class "Default")
      (node (ref "J3") (pin "4") (pinfunction "4_4") (pintype "passive"))
    )
    (net (code "84") (name "unconnected-(R5-Pad3)") (class "Default")
      (node (ref "R5") (pin "3") (pinfunction "3_3") (pintype "passive"))
    )
    (net (code "85") (name "unconnected-(SW1-ON-Pad1)") (class "Default")
      (node (ref "SW1") (pin "1") (pinfunction "ON_1") (pintype "passive"))
    )
    (net (code "86") (name "unconnected-(SW1-ON-Pad6)") (class "Default")
      (node (ref "SW1") (pin "6") (pinfunction "ON_6") (pintype "passive"))
    )
    (net (code "87") (name "unconnected-(U1-DIG4-Pad3)") (class "Default")
      (node (ref "U1") (pin "3") (pinfunction "DIG4_3") (pintype "passive"))
    )
    (net (code "88") (name "unconnected-(U1-DIG5-Pad10)") (class "Default")
      (node (ref "U1") (pin "10") (pinfunction "DIG5_10") (pintype "passive"))
    )
    (net (code "89") (name "unconnected-(U1-DIG6-Pad5)") (class "Default")
      (node (ref "U1") (pin "5") (pinfunction "DIG6_5") (pintype "passive"))
    )
    (net (code "90") (name "unconnected-(U1-DIG7-Pad8)") (class "Default")
      (node (ref "U1") (pin "8") (pinfunction "DIG7_8") (pintype "passive"))
    )
    (net (code "91") (name "unconnected-(U1-DOUT-Pad24)") (class "Default")
      (node (ref "U1") (pin "24") (pinfunction "DOUT_24") (pintype "passive"))
    )
    (net (code "92") (name "unconnected-(U3-CTS#-Pad9)") (class "Default")
      (node (ref "U3") (pin "9") (pinfunction "CTS#_9") (pintype "passive"))
    )
    (net (code "93") (name "unconnected-(U3-DCD#-Pad12)") (class "Default")
      (node (ref "U3") (pin "12") (pinfunction "DCD#_12") (pintype "passive"))
    )
    (net (code "94") (name "unconnected-(U3-DSR#-Pad10)") (class "Default")
      (node (ref "U3") (pin "10") (pinfunction "DSR#_10") (pintype "passive"))
    )
    (net (code "95") (name "unconnected-(U3-DTR#-Pad13)") (class "Default")
      (node (ref "U3") (pin "13") (pinfunction "DTR#_13") (pintype "passive"))
    )
    (net (code "96") (name "unconnected-(U3-R232-Pad15)") (class "Default")
      (node (ref "U3") (pin "15") (pinfunction "R232_15") (pintype "passive"))
    )
    (net (code "97") (name "unconnected-(U3-RI-Pad11)") (class "Default")
      (node (ref "U3") (pin "11") (pinfunction "RI_11") (pintype "passive"))
    )
    (net (code "98") (name "unconnected-(U3-RTS#-Pad14)") (class "Default")
      (node (ref "U3") (pin "14") (pinfunction "RTS#_14") (pintype "passive"))
    )
    (net (code "99") (name "unconnected-(USB1-ID-Pad4)") (class "Default")
      (node (ref "USB1") (pin "4") (pinfunction "ID_4") (pintype "passive"))
    )
    (net (code "100") (name "unconnected-(Y2-PadH1)") (class "Default")
      (node (ref "Y2") (pin "H1") (pinfunction "H1_H1") (pintype "passive"))
    )
  )
)
